# PL_PHY_RJ45.net
KiCad netlist of a schematic drawn in Altium Designer
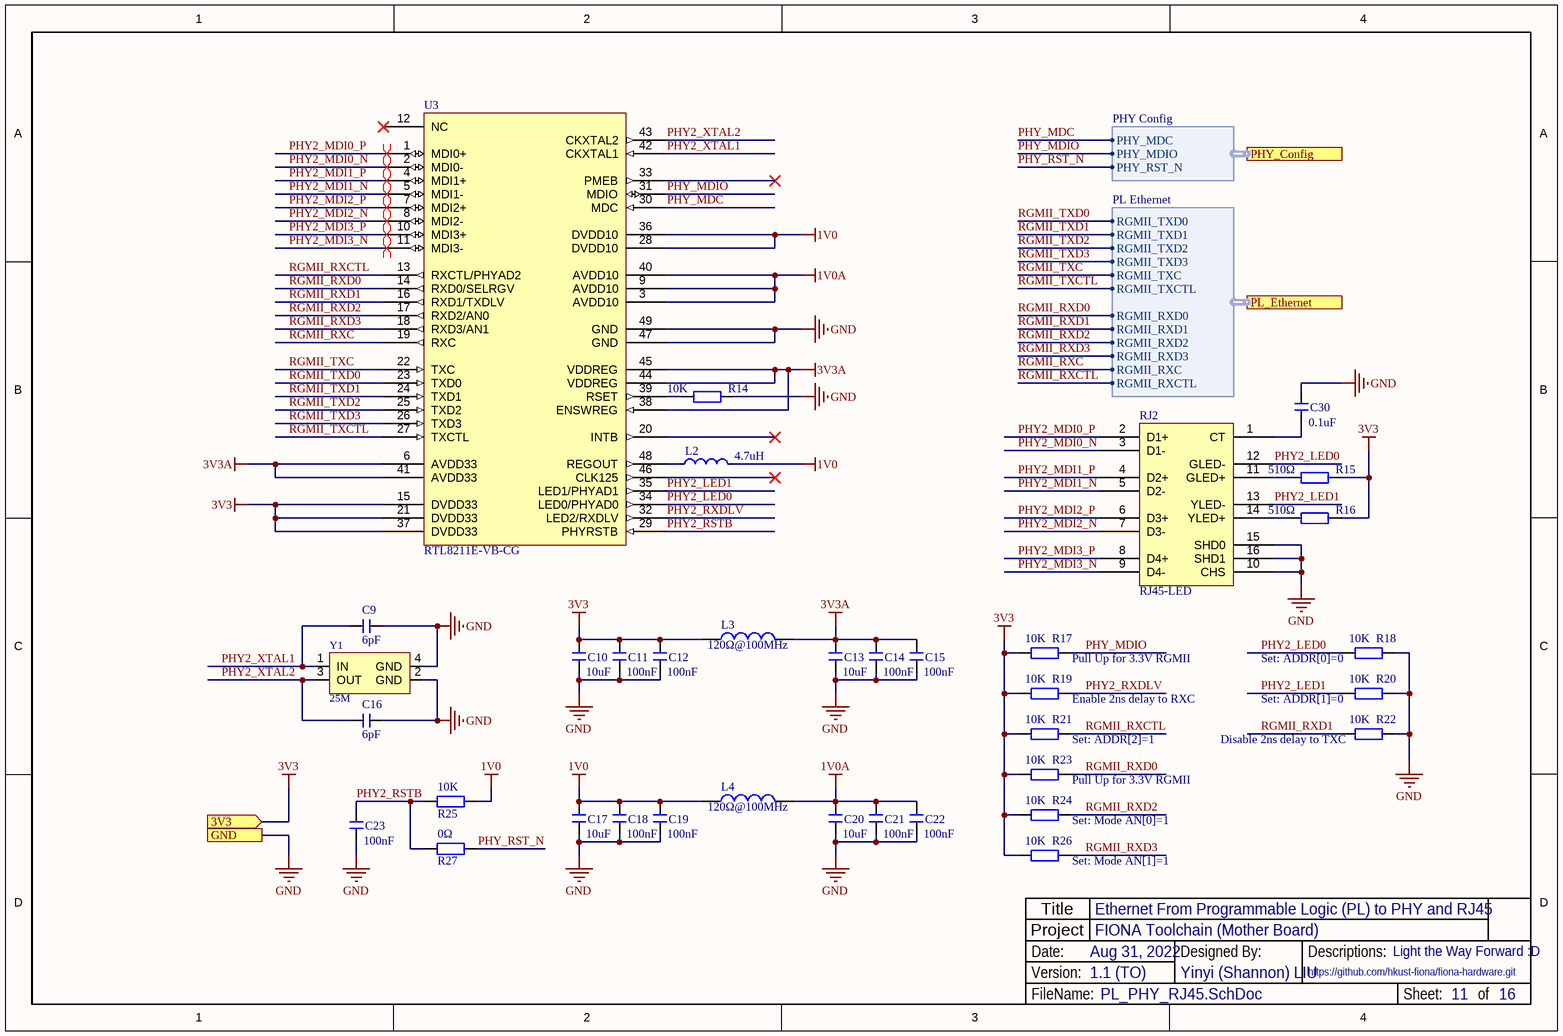
[diagram p0: PL_PHY_RJ45.SchDoc]

(export (version "E")
  (design (tool "Eeschema 10.0.6"))
  (components
    (comp (ref "C9")
      (value "6pF")
      (footprint "C 0402_L")
      (description "贴片电容")
      (libsource (lib "0.1 - 电阻-电容-电感") (part "C"))
    )
    (comp (ref "C10")
      (value "10uF")
      (footprint "C 0402_L")
      (description "贴片电容")
      (libsource (lib "0.1 - 电阻-电容-电感") (part "C"))
    )
    (comp (ref "C11")
      (value "100nF")
      (footprint "C 0402_L")
      (description "贴片电容")
      (libsource (lib "0.1 - 电阻-电容-电感") (part "C"))
    )
    (comp (ref "C12")
      (value "100nF")
      (footprint "C 0402_L")
      (description "贴片电容")
      (libsource (lib "0.1 - 电阻-电容-电感") (part "C"))
    )
    (comp (ref "C13")
      (value "10uF")
      (footprint "C 0402_L")
      (description "贴片电容")
      (libsource (lib "0.1 - 电阻-电容-电感") (part "C"))
    )
    (comp (ref "C14")
      (value "100nF")
      (footprint "C 0402_L")
      (description "贴片电容")
      (libsource (lib "0.1 - 电阻-电容-电感") (part "C"))
    )
    (comp (ref "C15")
      (value "100nF")
      (footprint "C 0402_L")
      (description "贴片电容")
      (libsource (lib "0.1 - 电阻-电容-电感") (part "C"))
    )
    (comp (ref "C16")
      (value "6pF")
      (footprint "C 0402_L")
      (description "贴片电容")
      (libsource (lib "0.1 - 电阻-电容-电感") (part "C"))
    )
    (comp (ref "C17")
      (value "10uF")
      (footprint "C 0402_L")
      (description "贴片电容")
      (libsource (lib "0.1 - 电阻-电容-电感") (part "C"))
    )
    (comp (ref "C18")
      (value "100nF")
      (footprint "C 0402_L")
      (description "贴片电容")
      (libsource (lib "0.1 - 电阻-电容-电感") (part "C"))
    )
    (comp (ref "C19")
      (value "100nF")
      (footprint "C 0402_L")
      (description "贴片电容")
      (libsource (lib "0.1 - 电阻-电容-电感") (part "C"))
    )
    (comp (ref "C20")
      (value "10uF")
      (footprint "C 0402_L")
      (description "贴片电容")
      (libsource (lib "0.1 - 电阻-电容-电感") (part "C"))
    )
    (comp (ref "C21")
      (value "100nF")
      (footprint "C 0402_L")
      (description "贴片电容")
      (libsource (lib "0.1 - 电阻-电容-电感") (part "C"))
    )
    (comp (ref "C22")
      (value "100nF")
      (footprint "C 0402_L")
      (description "贴片电容")
      (libsource (lib "0.1 - 电阻-电容-电感") (part "C"))
    )
    (comp (ref "C23")
      (value "100nF")
      (footprint "C 0201_L")
      (description "贴片电容")
      (libsource (lib "0.1 - 电阻-电容-电感") (part "C"))
    )
    (comp (ref "C30")
      (value "0.1uF")
      (footprint "C 0603_L")
      (description "贴片电容")
      (libsource (lib "0.1 - 电阻-电容-电感") (part "C"))
    )
    (comp (ref "L2")
      (value "Inductance SMD")
      (footprint "IND-SMD_L7.6-W6.6")
      (description "*LCID: C967698")
      (fields (field (name "INDUCTANCE") "4.7uH"))
      (libsource (lib "CustomizedComponents") (part "Inductance SMD"))
    )
    (comp (ref "L3")
      (value "120Ω@100MHz")
      (footprint "L 0603")
      (description "小功率贴片电感")
      (libsource (lib "0.1 - 电阻-电容-电感") (part "L"))
    )
    (comp (ref "L4")
      (value "120Ω@100MHz")
      (footprint "L 0603")
      (description "小功率贴片电感")
      (libsource (lib "0.1 - 电阻-电容-电感") (part "L"))
    )
    (comp (ref "R14")
      (value "10K")
      (footprint "R 0402_L")
      (description "贴片电阻")
      (fields (field (name "版权归属") "来自淘宝 ID：黄晶宝石"))
      (libsource (lib "0.1 - 电阻-电容-电感") (part "R"))
    )
    (comp (ref "R15")
      (value "510Ω")
      (footprint "R 0402_L")
      (description "贴片电阻")
      (fields (field (name "版权归属") "来自淘宝 ID：黄晶宝石"))
      (libsource (lib "0.1 - 电阻-电容-电感") (part "R"))
    )
    (comp (ref "R16")
      (value "510Ω")
      (footprint "R 0402_L")
      (description "贴片电阻")
      (fields (field (name "版权归属") "来自淘宝 ID：黄晶宝石"))
      (libsource (lib "0.1 - 电阻-电容-电感") (part "R"))
    )
    (comp (ref "R17")
      (value "10K")
      (footprint "R 0201_L")
      (description "贴片电阻")
      (fields (field (name "版权归属") "来自淘宝 ID：黄晶宝石"))
      (libsource (lib "0.1 - 电阻-电容-电感") (part "R"))
    )
    (comp (ref "R18")
      (value "10K")
      (footprint "R 0201_L")
      (description "贴片电阻")
      (fields (field (name "版权归属") "来自淘宝 ID：黄晶宝石"))
      (libsource (lib "0.1 - 电阻-电容-电感") (part "R"))
    )
    (comp (ref "R19")
      (value "10K")
      (footprint "R 0201_L")
      (description "贴片电阻")
      (fields (field (name "版权归属") "来自淘宝 ID：黄晶宝石"))
      (libsource (lib "0.1 - 电阻-电容-电感") (part "R"))
    )
    (comp (ref "R20")
      (value "10K")
      (footprint "R 0201_L")
      (description "贴片电阻")
      (fields (field (name "版权归属") "来自淘宝 ID：黄晶宝石"))
      (libsource (lib "0.1 - 电阻-电容-电感") (part "R"))
    )
    (comp (ref "R21")
      (value "10K")
      (footprint "R 0201_L")
      (description "贴片电阻")
      (fields (field (name "版权归属") "来自淘宝 ID：黄晶宝石"))
      (libsource (lib "0.1 - 电阻-电容-电感") (part "R"))
    )
    (comp (ref "R22")
      (value "10K")
      (footprint "R 0201_L")
      (description "贴片电阻")
      (fields (field (name "版权归属") "来自淘宝 ID：黄晶宝石"))
      (libsource (lib "0.1 - 电阻-电容-电感") (part "R"))
    )
    (comp (ref "R23")
      (value "10K")
      (footprint "R 0201_L")
      (description "贴片电阻")
      (fields (field (name "版权归属") "来自淘宝 ID：黄晶宝石"))
      (libsource (lib "0.1 - 电阻-电容-电感") (part "R"))
    )
    (comp (ref "R24")
      (value "10K")
      (footprint "R 0201_L")
      (description "贴片电阻")
      (fields (field (name "版权归属") "来自淘宝 ID：黄晶宝石"))
      (libsource (lib "0.1 - 电阻-电容-电感") (part "R"))
    )
    (comp (ref "R25")
      (value "10K")
      (footprint "R 0201_L")
      (description "贴片电阻")
      (fields (field (name "版权归属") "来自淘宝 ID：黄晶宝石"))
      (libsource (lib "0.1 - 电阻-电容-电感") (part "R"))
    )
    (comp (ref "R26")
      (value "10K")
      (footprint "R 0201_L")
      (description "贴片电阻")
      (fields (field (name "版权归属") "来自淘宝 ID：黄晶宝石"))
      (libsource (lib "0.1 - 电阻-电容-电感") (part "R"))
    )
    (comp (ref "R27")
      (value "0Ω")
      (footprint "R 0201_L")
      (description "贴片电阻")
      (fields (field (name "版权归属") "来自淘宝 ID：黄晶宝石"))
      (libsource (lib "0.1 - 电阻-电容-电感") (part "R"))
    )
    (comp (ref "RJ2")
      (value "RJ45-LED")
      (footprint "RJ-45A16")
      (description "带灯以太网接口")
      (fields (field (name "版权归属") "封装库来自淘宝 ID：黄晶宝石"))
      (libsource (lib "0.8 - 以太网-音频-USB插座") (part "RJ45-2LED"))
    )
    (comp (ref "U3")
      (value "RTL8211E-VB-CG")
      (footprint "QFN-48_L6.0-W6.0-P0.40")
      (description "Ethernet RGMII PHY Chip\r\n*LCID: C90735")
      (libsource (lib "CustomizedComponents") (part "RTL8211E-VB-CG"))
    )
    (comp (ref "Y1")
      (value "25M")
      (footprint "XTAL-3225")
      (description "4脚无源晶振")
      (fields (field (name "版权归属") "源创客"))
      (libsource (lib "领航者ZYNQ底板SCH&PCB封装库") (part "XTAL-4P"))
    )
  )
  (nets
    (net (code "5") (name "/PHY2_LED0") (class "Default")
      (node (ref "R18") (pin "1") (pinfunction "1_1") (pintype "passive"))
      (node (ref "RJ2") (pin "12") (pinfunction "GLED-_12") (pintype "passive"))
      (node (ref "U3") (pin "34") (pinfunction "LED0/PHYAD0_34") (pintype "output"))
    )
    (net (code "6") (name "/PHY2_LED1") (class "Default")
      (node (ref "R20") (pin "1") (pinfunction "1_1") (pintype "passive"))
      (node (ref "RJ2") (pin "13") (pinfunction "YLED-_13") (pintype "passive"))
      (node (ref "U3") (pin "35") (pinfunction "LED1/PHYAD1_35") (pintype "output"))
    )
    (net (code "7") (name "/PHY2_MDI0_N") (class "Default")
      (node (ref "RJ2") (pin "3") (pinfunction "D1-_3") (pintype "passive"))
      (node (ref "U3") (pin "2") (pinfunction "MDI0-_2") (pintype "bidirectional"))
    )
    (net (code "8") (name "/PHY2_MDI0_P") (class "Default")
      (node (ref "RJ2") (pin "2") (pinfunction "D1+_2") (pintype "passive"))
      (node (ref "U3") (pin "1") (pinfunction "MDI0+_1") (pintype "bidirectional"))
    )
    (net (code "9") (name "/PHY2_MDI1_N") (class "Default")
      (node (ref "RJ2") (pin "5") (pinfunction "D2-_5") (pintype "passive"))
      (node (ref "U3") (pin "5") (pinfunction "MDI1-_5") (pintype "bidirectional"))
    )
    (net (code "10") (name "/PHY2_MDI1_P") (class "Default")
      (node (ref "RJ2") (pin "4") (pinfunction "D2+_4") (pintype "passive"))
      (node (ref "U3") (pin "4") (pinfunction "MDI1+_4") (pintype "bidirectional"))
    )
    (net (code "11") (name "/PHY2_MDI2_N") (class "Default")
      (node (ref "RJ2") (pin "7") (pinfunction "D3-_7") (pintype "passive"))
      (node (ref "U3") (pin "8") (pinfunction "MDI2-_8") (pintype "bidirectional"))
    )
    (net (code "12") (name "/PHY2_MDI2_P") (class "Default")
      (node (ref "RJ2") (pin "6") (pinfunction "D3+_6") (pintype "passive"))
      (node (ref "U3") (pin "7") (pinfunction "MDI2+_7") (pintype "bidirectional"))
    )
    (net (code "13") (name "/PHY2_MDI3_N") (class "Default")
      (node (ref "RJ2") (pin "9") (pinfunction "D4-_9") (pintype "passive"))
      (node (ref "U3") (pin "11") (pinfunction "MDI3-_11") (pintype "bidirectional"))
    )
    (net (code "14") (name "/PHY2_MDI3_P") (class "Default")
      (node (ref "RJ2") (pin "8") (pinfunction "D4+_8") (pintype "passive"))
      (node (ref "U3") (pin "10") (pinfunction "MDI3+_10") (pintype "bidirectional"))
    )
    (net (code "15") (name "/PHY2_RSTB") (class "Default")
      (node (ref "C23") (pin "2") (pinfunction "2_2") (pintype "passive"))
      (node (ref "R25") (pin "1") (pinfunction "1_1") (pintype "passive"))
      (node (ref "R27") (pin "1") (pinfunction "1_1") (pintype "passive"))
      (node (ref "U3") (pin "29") (pinfunction "PHYRSTB_29") (pintype "input"))
    )
    (net (code "16") (name "/PHY2_RXDLV") (class "Default")
      (node (ref "R19") (pin "2") (pinfunction "2_2") (pintype "passive"))
      (node (ref "U3") (pin "32") (pinfunction "LED2/RXDLV_32") (pintype "output"))
    )
    (net (code "17") (name "/PHY2_XTAL1") (class "Default")
      (node (ref "C9") (pin "1") (pinfunction "1_1") (pintype "passive"))
      (node (ref "U3") (pin "42") (pinfunction "CKXTAL1_42") (pintype "input"))
      (node (ref "Y1") (pin "1") (pinfunction "IN_1") (pintype "passive"))
    )
    (net (code "18") (name "/PHY2_XTAL2") (class "Default")
      (node (ref "C16") (pin "1") (pinfunction "1_1") (pintype "passive"))
      (node (ref "U3") (pin "43") (pinfunction "CKXTAL2_43") (pintype "output"))
      (node (ref "Y1") (pin "3") (pinfunction "OUT_3") (pintype "passive"))
    )
    (net (code "19") (name "/PHY_MDC") (class "Default")
      (node (ref "U3") (pin "30") (pinfunction "MDC_30") (pintype "input"))
    )
    (net (code "20") (name "/PHY_MDIO") (class "Default")
      (node (ref "R17") (pin "2") (pinfunction "2_2") (pintype "passive"))
      (node (ref "U3") (pin "31") (pinfunction "MDIO_31") (pintype "bidirectional"))
    )
    (net (code "21") (name "/PHY_RST_N") (class "Default")
      (node (ref "R27") (pin "2") (pinfunction "2_2") (pintype "passive"))
    )
    (net (code "22") (name "/RGMII_RXC") (class "Default")
      (node (ref "U3") (pin "19") (pinfunction "RXC_19") (pintype "output"))
    )
    (net (code "23") (name "/RGMII_RXCTL") (class "Default")
      (node (ref "R21") (pin "2") (pinfunction "2_2") (pintype "passive"))
      (node (ref "U3") (pin "13") (pinfunction "RXCTL/PHYAD2_13") (pintype "output"))
    )
    (net (code "24") (name "/RGMII_RXD0") (class "Default")
      (node (ref "R23") (pin "2") (pinfunction "2_2") (pintype "passive"))
      (node (ref "U3") (pin "14") (pinfunction "RXD0/SELRGV_14") (pintype "output"))
    )
    (net (code "25") (name "/RGMII_RXD1") (class "Default")
      (node (ref "R22") (pin "1") (pinfunction "1_1") (pintype "passive"))
      (node (ref "U3") (pin "16") (pinfunction "RXD1/TXDLV_16") (pintype "output"))
    )
    (net (code "26") (name "/RGMII_RXD2") (class "Default")
      (node (ref "R24") (pin "2") (pinfunction "2_2") (pintype "passive"))
      (node (ref "U3") (pin "17") (pinfunction "RXD2/AN0_17") (pintype "output"))
    )
    (net (code "27") (name "/RGMII_RXD3") (class "Default")
      (node (ref "R26") (pin "2") (pinfunction "2_2") (pintype "passive"))
      (node (ref "U3") (pin "18") (pinfunction "RXD3/AN1_18") (pintype "output"))
    )
    (net (code "28") (name "/RGMII_TXC") (class "Default")
      (node (ref "U3") (pin "22") (pinfunction "TXC_22") (pintype "input"))
    )
    (net (code "29") (name "/RGMII_TXCTL") (class "Default")
      (node (ref "U3") (pin "27") (pinfunction "TXCTL_27") (pintype "input"))
    )
    (net (code "30") (name "/RGMII_TXD0") (class "Default")
      (node (ref "U3") (pin "23") (pinfunction "TXD0_23") (pintype "input"))
    )
    (net (code "31") (name "/RGMII_TXD1") (class "Default")
      (node (ref "U3") (pin "24") (pinfunction "TXD1_24") (pintype "input"))
    )
    (net (code "32") (name "/RGMII_TXD2") (class "Default")
      (node (ref "U3") (pin "25") (pinfunction "TXD2_25") (pintype "input"))
    )
    (net (code "33") (name "/RGMII_TXD3") (class "Default")
      (node (ref "U3") (pin "26") (pinfunction "TXD3_26") (pintype "input"))
    )
    (net (code "36") (name "1V0") (class "Default")
      (node (ref "C17") (pin "2") (pinfunction "2_2") (pintype "passive"))
      (node (ref "C18") (pin "2") (pinfunction "2_2") (pintype "passive"))
      (node (ref "C19") (pin "2") (pinfunction "2_2") (pintype "passive"))
      (node (ref "L2") (pin "2") (pintype "passive"))
      (node (ref "L4") (pin "1") (pinfunction "1_1") (pintype "passive"))
      (node (ref "R25") (pin "2") (pinfunction "2_2") (pintype "passive"))
      (node (ref "U3") (pin "28") (pinfunction "DVDD10_28") (pintype "power_in"))
      (node (ref "U3") (pin "36") (pinfunction "DVDD10_36") (pintype "power_in"))
    )
    (net (code "37") (name "1V0A") (class "Default")
      (node (ref "C20") (pin "2") (pinfunction "2_2") (pintype "passive"))
      (node (ref "C21") (pin "2") (pinfunction "2_2") (pintype "passive"))
      (node (ref "C22") (pin "2") (pinfunction "2_2") (pintype "passive"))
      (node (ref "L4") (pin "2") (pinfunction "2_2") (pintype "passive"))
      (node (ref "U3") (pin "3") (pinfunction "AVDD10_3") (pintype "power_in"))
      (node (ref "U3") (pin "40") (pinfunction "AVDD10_40") (pintype "power_in"))
      (node (ref "U3") (pin "9") (pinfunction "AVDD10_9") (pintype "power_in"))
    )
    (net (code "38") (name "3V3") (class "Default")
      (node (ref "C10") (pin "2") (pinfunction "2_2") (pintype "passive"))
      (node (ref "C11") (pin "2") (pinfunction "2_2") (pintype "passive"))
      (node (ref "C12") (pin "2") (pinfunction "2_2") (pintype "passive"))
      (node (ref "L3") (pin "1") (pinfunction "1_1") (pintype "passive"))
      (node (ref "R15") (pin "2") (pinfunction "2_2") (pintype "passive"))
      (node (ref "R16") (pin "2") (pinfunction "2_2") (pintype "passive"))
      (node (ref "R17") (pin "1") (pinfunction "1_1") (pintype "passive"))
      (node (ref "R19") (pin "1") (pinfunction "1_1") (pintype "passive"))
      (node (ref "R21") (pin "1") (pinfunction "1_1") (pintype "passive"))
      (node (ref "R23") (pin "1") (pinfunction "1_1") (pintype "passive"))
      (node (ref "R24") (pin "1") (pinfunction "1_1") (pintype "passive"))
      (node (ref "R26") (pin "1") (pinfunction "1_1") (pintype "passive"))
      (node (ref "U3") (pin "15") (pinfunction "DVDD33_15") (pintype "power_in"))
      (node (ref "U3") (pin "21") (pinfunction "DVDD33_21") (pintype "power_in"))
      (node (ref "U3") (pin "37") (pinfunction "DVDD33_37") (pintype "power_in"))
    )
    (net (code "39") (name "3V3A") (class "Default")
      (node (ref "C13") (pin "2") (pinfunction "2_2") (pintype "passive"))
      (node (ref "C14") (pin "2") (pinfunction "2_2") (pintype "passive"))
      (node (ref "C15") (pin "2") (pinfunction "2_2") (pintype "passive"))
      (node (ref "L3") (pin "2") (pinfunction "2_2") (pintype "passive"))
      (node (ref "U3") (pin "38") (pinfunction "ENSWREG_38") (pintype "input"))
      (node (ref "U3") (pin "41") (pinfunction "AVDD33_41") (pintype "power_in"))
      (node (ref "U3") (pin "44") (pinfunction "VDDREG_44") (pintype "power_in"))
      (node (ref "U3") (pin "45") (pinfunction "VDDREG_45") (pintype "power_in"))
      (node (ref "U3") (pin "6") (pinfunction "AVDD33_6") (pintype "power_in"))
    )
    (net (code "40") (name "GND") (class "Default")
      (node (ref "C10") (pin "1") (pinfunction "1_1") (pintype "passive"))
      (node (ref "C11") (pin "1") (pinfunction "1_1") (pintype "passive"))
      (node (ref "C12") (pin "1") (pinfunction "1_1") (pintype "passive"))
      (node (ref "C13") (pin "1") (pinfunction "1_1") (pintype "passive"))
      (node (ref "C14") (pin "1") (pinfunction "1_1") (pintype "passive"))
      (node (ref "C15") (pin "1") (pinfunction "1_1") (pintype "passive"))
      (node (ref "C16") (pin "2") (pinfunction "2_2") (pintype "passive"))
      (node (ref "C17") (pin "1") (pinfunction "1_1") (pintype "passive"))
      (node (ref "C18") (pin "1") (pinfunction "1_1") (pintype "passive"))
      (node (ref "C19") (pin "1") (pinfunction "1_1") (pintype "passive"))
      (node (ref "C20") (pin "1") (pinfunction "1_1") (pintype "passive"))
      (node (ref "C21") (pin "1") (pinfunction "1_1") (pintype "passive"))
      (node (ref "C22") (pin "1") (pinfunction "1_1") (pintype "passive"))
      (node (ref "C23") (pin "1") (pinfunction "1_1") (pintype "passive"))
      (node (ref "C30") (pin "2") (pinfunction "2_2") (pintype "passive"))
      (node (ref "C9") (pin "2") (pinfunction "2_2") (pintype "passive"))
      (node (ref "R14") (pin "2") (pinfunction "2_2") (pintype "passive"))
      (node (ref "R18") (pin "2") (pinfunction "2_2") (pintype "passive"))
      (node (ref "R20") (pin "2") (pinfunction "2_2") (pintype "passive"))
      (node (ref "R22") (pin "2") (pinfunction "2_2") (pintype "passive"))
      (node (ref "RJ2") (pin "10") (pinfunction "CHS_10") (pintype "passive"))
      (node (ref "RJ2") (pin "15") (pinfunction "SHD0_15") (pintype "passive"))
      (node (ref "RJ2") (pin "16") (pinfunction "SHD1_16") (pintype "passive"))
      (node (ref "U3") (pin "47") (pinfunction "GND_47") (pintype "power_in"))
      (node (ref "U3") (pin "49") (pinfunction "GND_49") (pintype "power_in"))
      (node (ref "Y1") (pin "2") (pinfunction "GND_2") (pintype "passive"))
      (node (ref "Y1") (pin "4") (pinfunction "GND_4") (pintype "passive"))
    )
    (net (code "41") (name "Net-(RJ2-CT)") (class "Default")
      (node (ref "C30") (pin "1") (pinfunction "1_1") (pintype "passive"))
      (node (ref "RJ2") (pin "1") (pinfunction "CT_1") (pintype "passive"))
    )
    (net (code "42") (name "Net-(RJ2-GLED+)") (class "Default")
      (node (ref "R15") (pin "1") (pinfunction "1_1") (pintype "passive"))
      (node (ref "RJ2") (pin "11") (pinfunction "GLED+_11") (pintype "passive"))
    )
    (net (code "43") (name "Net-(RJ2-YLED+)") (class "Default")
      (node (ref "R16") (pin "1") (pinfunction "1_1") (pintype "passive"))
      (node (ref "RJ2") (pin "14") (pinfunction "YLED+_14") (pintype "passive"))
    )
    (net (code "44") (name "Net-(U3-REGOUT)") (class "Default")
      (node (ref "L2") (pin "1") (pintype "passive"))
      (node (ref "U3") (pin "48") (pinfunction "REGOUT_48") (pintype "output"))
    )
    (net (code "45") (name "Net-(U3-RSET)") (class "Default")
      (node (ref "R14") (pin "1") (pinfunction "1_1") (pintype "passive"))
      (node (ref "U3") (pin "39") (pinfunction "RSET_39") (pintype "output"))
    )
    (net (code "46") (name "unconnected-(U3-CLK125-Pad46)") (class "Default")
      (node (ref "U3") (pin "46") (pinfunction "CLK125_46") (pintype "output+no_connect"))
    )
    (net (code "47") (name "unconnected-(U3-INTB-Pad20)") (class "Default")
      (node (ref "U3") (pin "20") (pinfunction "INTB_20") (pintype "output+no_connect"))
    )
    (net (code "48") (name "unconnected-(U3-NC-Pad12)") (class "Default")
      (node (ref "U3") (pin "12") (pinfunction "NC_12") (pintype "passive+no_connect"))
    )
    (net (code "49") (name "unconnected-(U3-PMEB-Pad33)") (class "Default")
      (node (ref "U3") (pin "33") (pinfunction "PMEB_33") (pintype "output+no_connect"))
    )
  )
)
